# rev4.net
KiCad netlist of a schematic drawn in Altium Designer
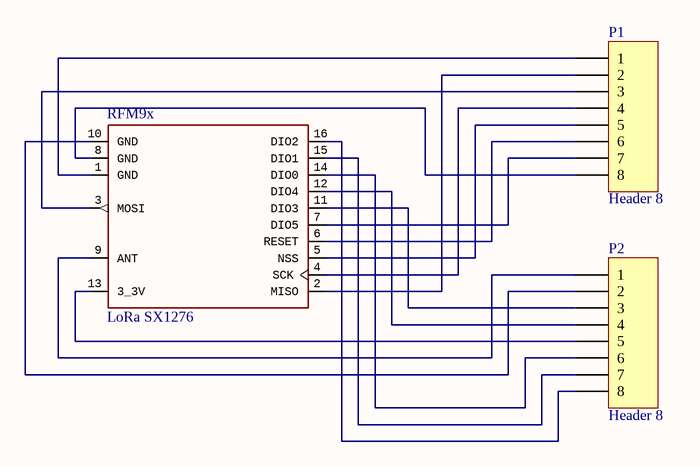
[diagram p0: rev4.SchDoc]

(export (version "E")
  (design (tool "Eeschema 10.0.6"))
  (components
    (comp (ref "P1")
      (value "Header 8")
      (footprint "HDR1X8")
      (description "Header, 8-Pin")
      (fields (field (name "PUBLISHER") "Altium Limited"))
      (libsource (lib "Miscellaneous Connectors") (part "Header 8"))
    )
    (comp (ref "P2")
      (value "Header 8")
      (footprint "HDR1X8")
      (description "Header, 8-Pin")
      (fields (field (name "PUBLISHER") "Altium Limited"))
      (libsource (lib "Miscellaneous Connectors") (part "Header 8"))
    )
    (comp (ref "RFM9x")
      (value "LoRa SX1276")
      (footprint "XCVR_RFM95W-868S2")
      (fields (field (name "MF") "RF") (field (name "MP") "RFM95W-868S2"))
      (libsource (lib "RFM95rev1") (part "RFM95W-868S2"))
    )
  )
  (nets
    (net (code "1") (name "Net-(P1-Pad1)") (class "Default")
      (node (ref "P1") (pin "1") (pinfunction "1_1") (pintype "passive"))
      (node (ref "RFM9x") (pin "1") (pinfunction "GND_1") (pintype "power_in"))
    )
    (net (code "2") (name "Net-(P1-Pad8)") (class "Default")
      (node (ref "P1") (pin "8") (pinfunction "8_8") (pintype "passive"))
      (node (ref "RFM9x") (pin "8") (pinfunction "GND_8") (pintype "power_in"))
    )
    (net (code "3") (name "Net-(P2-Pad2)") (class "Default")
      (node (ref "P2") (pin "2") (pinfunction "2_2") (pintype "passive"))
      (node (ref "RFM9x") (pin "10") (pinfunction "GND_10") (pintype "power_in"))
    )
    (net (code "4") (name "Net-(RFM9x-3_3V)") (class "Default")
      (node (ref "P2") (pin "5") (pinfunction "5_5") (pintype "passive"))
      (node (ref "RFM9x") (pin "13") (pinfunction "3_3V_13") (pintype "power_in"))
    )
    (net (code "5") (name "Net-(RFM9x-ANT)") (class "Default")
      (node (ref "P2") (pin "1") (pinfunction "1_1") (pintype "passive"))
      (node (ref "RFM9x") (pin "9") (pinfunction "ANT_9") (pintype "passive"))
    )
    (net (code "6") (name "Net-(RFM9x-DIO0)") (class "Default")
      (node (ref "P2") (pin "6") (pinfunction "6_6") (pintype "passive"))
      (node (ref "RFM9x") (pin "14") (pinfunction "DIO0_14") (pintype "passive"))
    )
    (net (code "7") (name "Net-(RFM9x-DIO1)") (class "Default")
      (node (ref "P2") (pin "7") (pinfunction "7_7") (pintype "passive"))
      (node (ref "RFM9x") (pin "15") (pinfunction "DIO1_15") (pintype "passive"))
    )
    (net (code "8") (name "Net-(RFM9x-DIO2)") (class "Default")
      (node (ref "P2") (pin "8") (pinfunction "8_8") (pintype "passive"))
      (node (ref "RFM9x") (pin "16") (pinfunction "DIO2_16") (pintype "passive"))
    )
    (net (code "9") (name "Net-(RFM9x-DIO3)") (class "Default")
      (node (ref "P2") (pin "3") (pinfunction "3_3") (pintype "passive"))
      (node (ref "RFM9x") (pin "11") (pinfunction "DIO3_11") (pintype "passive"))
    )
    (net (code "10") (name "Net-(RFM9x-DIO4)") (class "Default")
      (node (ref "P2") (pin "4") (pinfunction "4_4") (pintype "passive"))
      (node (ref "RFM9x") (pin "12") (pinfunction "DIO4_12") (pintype "passive"))
    )
    (net (code "11") (name "Net-(RFM9x-DIO5)") (class "Default")
      (node (ref "P1") (pin "7") (pinfunction "7_7") (pintype "passive"))
      (node (ref "RFM9x") (pin "7") (pinfunction "DIO5_7") (pintype "passive"))
    )
    (net (code "12") (name "Net-(RFM9x-MISO)") (class "Default")
      (node (ref "P1") (pin "2") (pinfunction "2_2") (pintype "passive"))
      (node (ref "RFM9x") (pin "2") (pinfunction "MISO_2") (pintype "passive"))
    )
    (net (code "13") (name "Net-(RFM9x-MOSI)") (class "Default")
      (node (ref "P1") (pin "3") (pinfunction "3_3") (pintype "passive"))
      (node (ref "RFM9x") (pin "3") (pinfunction "MOSI_3") (pintype "output"))
    )
    (net (code "14") (name "Net-(RFM9x-NSS)") (class "Default")
      (node (ref "P1") (pin "5") (pinfunction "5_5") (pintype "passive"))
      (node (ref "RFM9x") (pin "5") (pinfunction "NSS_5") (pintype "passive"))
    )
    (net (code "15") (name "Net-(RFM9x-RESET)") (class "Default")
      (node (ref "P1") (pin "6") (pinfunction "6_6") (pintype "passive"))
      (node (ref "RFM9x") (pin "6") (pinfunction "RESET_6") (pintype "passive"))
    )
    (net (code "16") (name "Net-(RFM9x-SCK)") (class "Default")
      (node (ref "P1") (pin "4") (pinfunction "4_4") (pintype "passive"))
      (node (ref "RFM9x") (pin "4") (pinfunction "SCK_4") (pintype "passive"))
    )
  )
)
